# Sheet2.net
KiCad netlist of a schematic drawn in Altium Designer
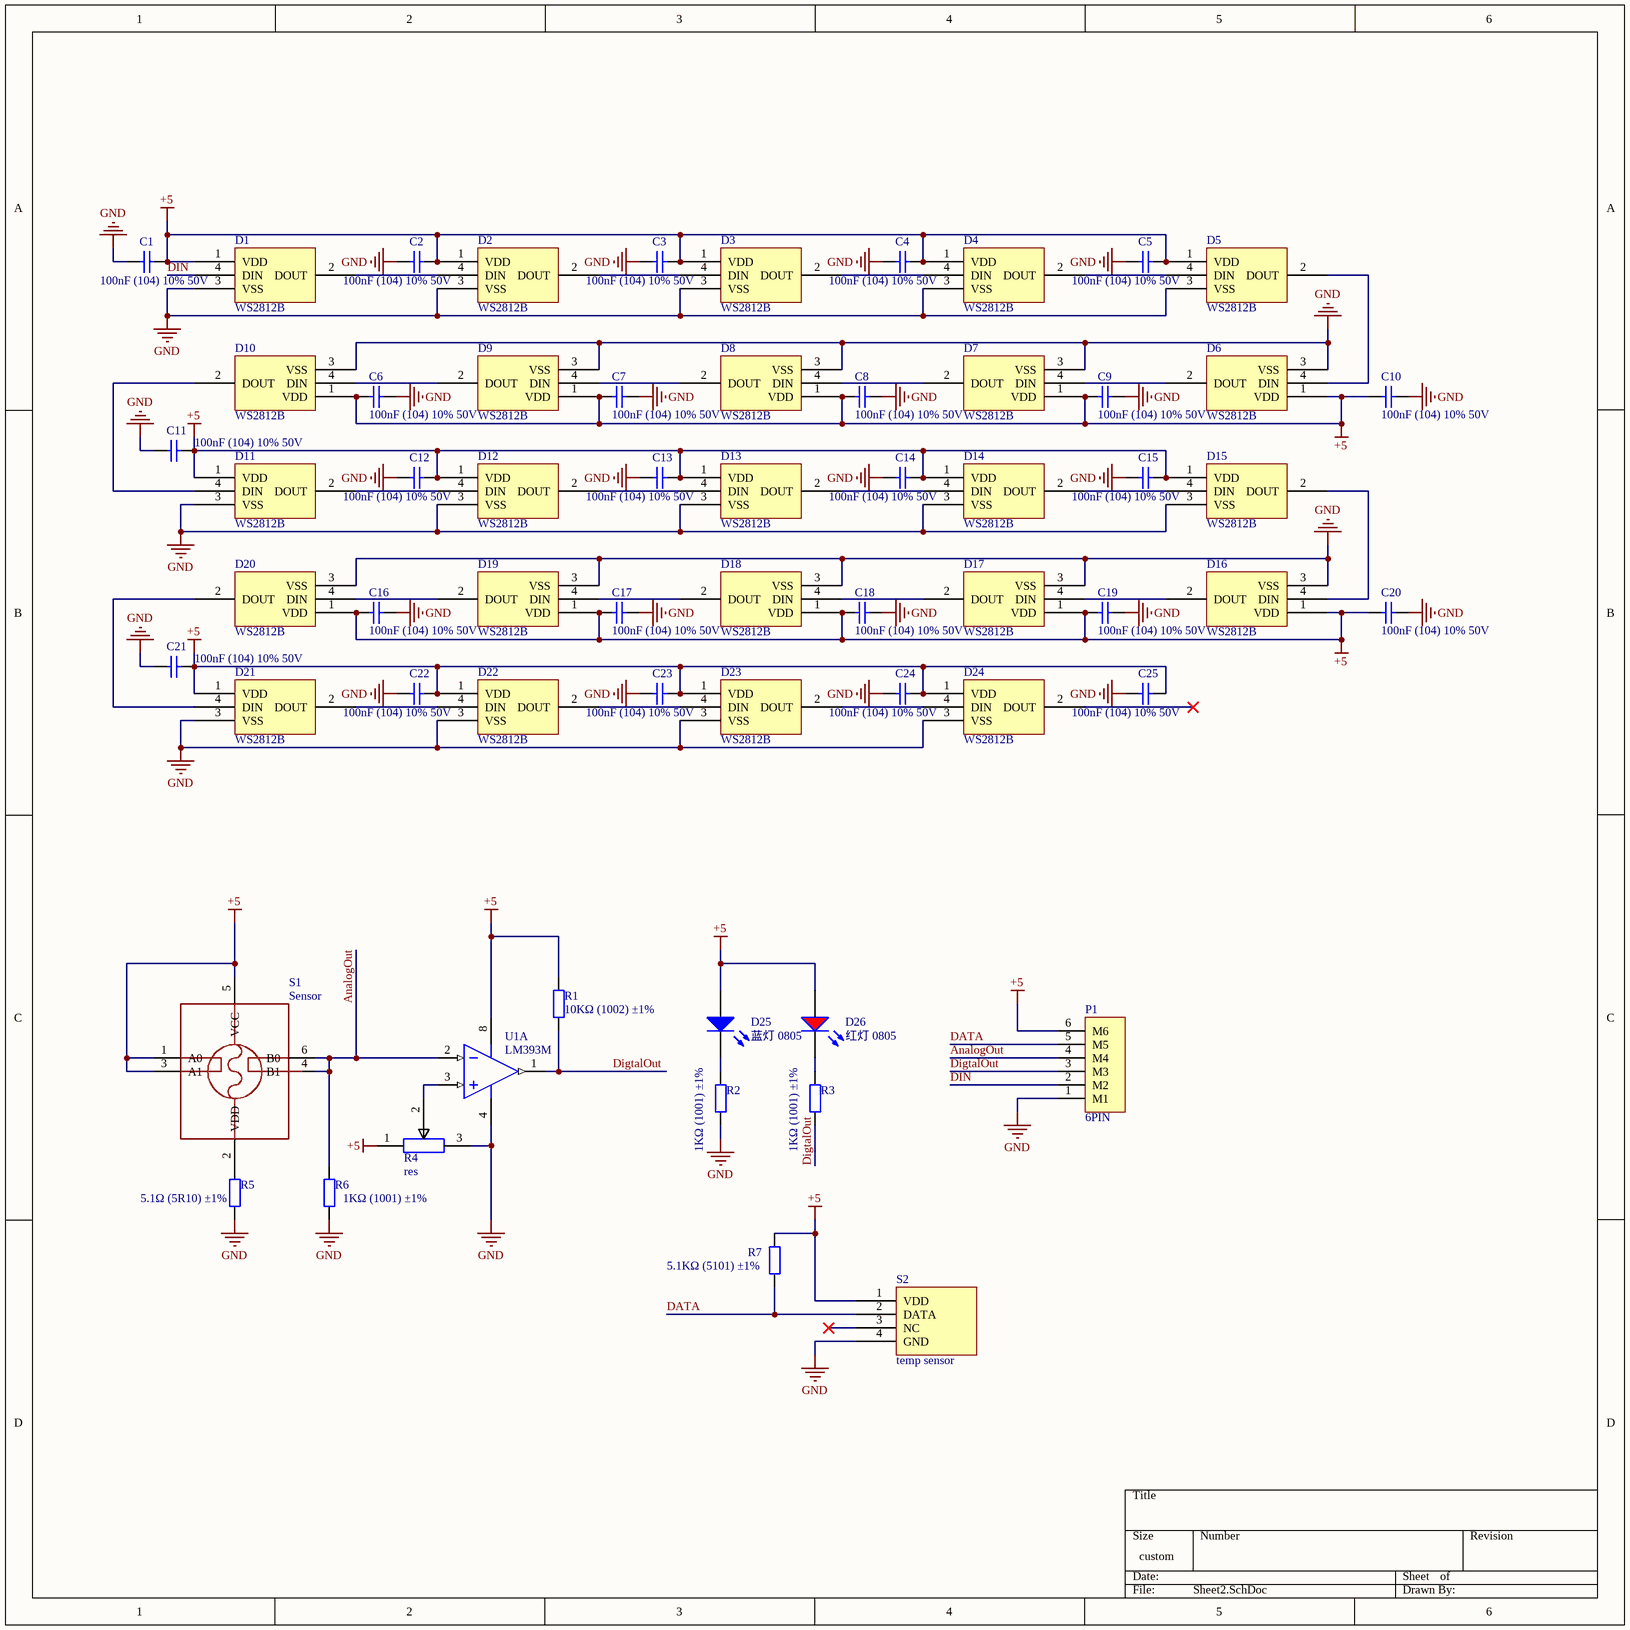
[diagram p0: Sheet2.SchDoc]

(export (version "E")
  (design (tool "Eeschema 10.0.6"))
  (components
    (comp (ref "C1")
      (value "100nF (104) 10% 50V")
      (footprint "0603_C")
      (description "贴片电容")
      (libsource (lib "Cap") (part "0603 100nF (104) 10% 50V"))
    )
    (comp (ref "C2")
      (value "100nF (104) 10% 50V")
      (footprint "0603_C")
      (description "贴片电容")
      (libsource (lib "Cap") (part "0603 100nF (104) 10% 50V"))
    )
    (comp (ref "C3")
      (value "100nF (104) 10% 50V")
      (footprint "0603_C")
      (description "贴片电容")
      (libsource (lib "Cap") (part "0603 100nF (104) 10% 50V"))
    )
    (comp (ref "C4")
      (value "100nF (104) 10% 50V")
      (footprint "0603_C")
      (description "贴片电容")
      (libsource (lib "Cap") (part "0603 100nF (104) 10% 50V"))
    )
    (comp (ref "C5")
      (value "100nF (104) 10% 50V")
      (footprint "0603_C")
      (description "贴片电容")
      (libsource (lib "Cap") (part "0603 100nF (104) 10% 50V"))
    )
    (comp (ref "C6")
      (value "100nF (104) 10% 50V")
      (footprint "0603_C")
      (description "贴片电容")
      (libsource (lib "Cap") (part "0603 100nF (104) 10% 50V"))
    )
    (comp (ref "C7")
      (value "100nF (104) 10% 50V")
      (footprint "0603_C")
      (description "贴片电容")
      (libsource (lib "Cap") (part "0603 100nF (104) 10% 50V"))
    )
    (comp (ref "C8")
      (value "100nF (104) 10% 50V")
      (footprint "0603_C")
      (description "贴片电容")
      (libsource (lib "Cap") (part "0603 100nF (104) 10% 50V"))
    )
    (comp (ref "C9")
      (value "100nF (104) 10% 50V")
      (footprint "0603_C")
      (description "贴片电容")
      (libsource (lib "Cap") (part "0603 100nF (104) 10% 50V"))
    )
    (comp (ref "C10")
      (value "100nF (104) 10% 50V")
      (footprint "0603_C")
      (description "贴片电容")
      (libsource (lib "Cap") (part "0603 100nF (104) 10% 50V"))
    )
    (comp (ref "C11")
      (value "100nF (104) 10% 50V")
      (footprint "0603_C")
      (description "贴片电容")
      (libsource (lib "Cap") (part "0603 100nF (104) 10% 50V"))
    )
    (comp (ref "C12")
      (value "100nF (104) 10% 50V")
      (footprint "0603_C")
      (description "贴片电容")
      (libsource (lib "Cap") (part "0603 100nF (104) 10% 50V"))
    )
    (comp (ref "C13")
      (value "100nF (104) 10% 50V")
      (footprint "0603_C")
      (description "贴片电容")
      (libsource (lib "Cap") (part "0603 100nF (104) 10% 50V"))
    )
    (comp (ref "C14")
      (value "100nF (104) 10% 50V")
      (footprint "0603_C")
      (description "贴片电容")
      (libsource (lib "Cap") (part "0603 100nF (104) 10% 50V"))
    )
    (comp (ref "C15")
      (value "100nF (104) 10% 50V")
      (footprint "0603_C")
      (description "贴片电容")
      (libsource (lib "Cap") (part "0603 100nF (104) 10% 50V"))
    )
    (comp (ref "C16")
      (value "100nF (104) 10% 50V")
      (footprint "0603_C")
      (description "贴片电容")
      (libsource (lib "Cap") (part "0603 100nF (104) 10% 50V"))
    )
    (comp (ref "C17")
      (value "100nF (104) 10% 50V")
      (footprint "0603_C")
      (description "贴片电容")
      (libsource (lib "Cap") (part "0603 100nF (104) 10% 50V"))
    )
    (comp (ref "C18")
      (value "100nF (104) 10% 50V")
      (footprint "0603_C")
      (description "贴片电容")
      (libsource (lib "Cap") (part "0603 100nF (104) 10% 50V"))
    )
    (comp (ref "C19")
      (value "100nF (104) 10% 50V")
      (footprint "0603_C")
      (description "贴片电容")
      (libsource (lib "Cap") (part "0603 100nF (104) 10% 50V"))
    )
    (comp (ref "C20")
      (value "100nF (104) 10% 50V")
      (footprint "0603_C")
      (description "贴片电容")
      (libsource (lib "Cap") (part "0603 100nF (104) 10% 50V"))
    )
    (comp (ref "C21")
      (value "100nF (104) 10% 50V")
      (footprint "0603_C")
      (description "贴片电容")
      (libsource (lib "Cap") (part "0603 100nF (104) 10% 50V"))
    )
    (comp (ref "C22")
      (value "100nF (104) 10% 50V")
      (footprint "0603_C")
      (description "贴片电容")
      (libsource (lib "Cap") (part "0603 100nF (104) 10% 50V"))
    )
    (comp (ref "C23")
      (value "100nF (104) 10% 50V")
      (footprint "0603_C")
      (description "贴片电容")
      (libsource (lib "Cap") (part "0603 100nF (104) 10% 50V"))
    )
    (comp (ref "C24")
      (value "100nF (104) 10% 50V")
      (footprint "0603_C")
      (description "贴片电容")
      (libsource (lib "Cap") (part "0603 100nF (104) 10% 50V"))
    )
    (comp (ref "C25")
      (value "100nF (104) 10% 50V")
      (footprint "0603_C")
      (description "贴片电容")
      (libsource (lib "Cap") (part "0603 100nF (104) 10% 50V"))
    )
    (comp (ref "D1")
      (value "WS2812B")
      (footprint "5050-4PIN-WS2812")
      (description "RGB LED IC")
      (libsource (lib "") (part "WS2812B_1"))
    )
    (comp (ref "D2")
      (value "WS2812B")
      (footprint "5050-4PIN-WS2812")
      (description "RGB LED IC")
      (libsource (lib "") (part "WS2812B_1"))
    )
    (comp (ref "D3")
      (value "WS2812B")
      (footprint "5050-4PIN-WS2812")
      (description "RGB LED IC")
      (libsource (lib "") (part "WS2812B_1"))
    )
    (comp (ref "D4")
      (value "WS2812B")
      (footprint "5050-4PIN-WS2812")
      (description "RGB LED IC")
      (libsource (lib "") (part "WS2812B_1"))
    )
    (comp (ref "D5")
      (value "WS2812B")
      (footprint "5050-4PIN-WS2812")
      (description "RGB LED IC")
      (libsource (lib "") (part "WS2812B_1"))
    )
    (comp (ref "D6")
      (value "WS2812B")
      (footprint "5050-4PIN-WS2812")
      (description "RGB LED IC")
      (libsource (lib "RGB") (part "WS2812B"))
    )
    (comp (ref "D7")
      (value "WS2812B")
      (footprint "5050-4PIN-WS2812")
      (description "RGB LED IC")
      (libsource (lib "RGB") (part "WS2812B"))
    )
    (comp (ref "D8")
      (value "WS2812B")
      (footprint "5050-4PIN-WS2812")
      (description "RGB LED IC")
      (libsource (lib "RGB") (part "WS2812B"))
    )
    (comp (ref "D9")
      (value "WS2812B")
      (footprint "5050-4PIN-WS2812")
      (description "RGB LED IC")
      (libsource (lib "RGB") (part "WS2812B"))
    )
    (comp (ref "D10")
      (value "WS2812B")
      (footprint "5050-4PIN-WS2812")
      (description "RGB LED IC")
      (libsource (lib "RGB") (part "WS2812B"))
    )
    (comp (ref "D11")
      (value "WS2812B")
      (footprint "5050-4PIN-WS2812")
      (description "RGB LED IC")
      (libsource (lib "") (part "WS2812B_1"))
    )
    (comp (ref "D12")
      (value "WS2812B")
      (footprint "5050-4PIN-WS2812")
      (description "RGB LED IC")
      (libsource (lib "") (part "WS2812B_1"))
    )
    (comp (ref "D13")
      (value "WS2812B")
      (footprint "5050-4PIN-WS2812")
      (description "RGB LED IC")
      (libsource (lib "") (part "WS2812B_1"))
    )
    (comp (ref "D14")
      (value "WS2812B")
      (footprint "5050-4PIN-WS2812")
      (description "RGB LED IC")
      (libsource (lib "") (part "WS2812B_1"))
    )
    (comp (ref "D15")
      (value "WS2812B")
      (footprint "5050-4PIN-WS2812")
      (description "RGB LED IC")
      (libsource (lib "") (part "WS2812B_1"))
    )
    (comp (ref "D16")
      (value "WS2812B")
      (footprint "5050-4PIN-WS2812")
      (description "RGB LED IC")
      (libsource (lib "RGB") (part "WS2812B"))
    )
    (comp (ref "D17")
      (value "WS2812B")
      (footprint "5050-4PIN-WS2812")
      (description "RGB LED IC")
      (libsource (lib "RGB") (part "WS2812B"))
    )
    (comp (ref "D18")
      (value "WS2812B")
      (footprint "5050-4PIN-WS2812")
      (description "RGB LED IC")
      (libsource (lib "RGB") (part "WS2812B"))
    )
    (comp (ref "D19")
      (value "WS2812B")
      (footprint "5050-4PIN-WS2812")
      (description "RGB LED IC")
      (libsource (lib "RGB") (part "WS2812B"))
    )
    (comp (ref "D20")
      (value "WS2812B")
      (footprint "5050-4PIN-WS2812")
      (description "RGB LED IC")
      (libsource (lib "RGB") (part "WS2812B"))
    )
    (comp (ref "D21")
      (value "WS2812B")
      (footprint "5050-4PIN-WS2812")
      (description "RGB LED IC")
      (libsource (lib "") (part "WS2812B_1"))
    )
    (comp (ref "D22")
      (value "WS2812B")
      (footprint "5050-4PIN-WS2812")
      (description "RGB LED IC")
      (libsource (lib "") (part "WS2812B_1"))
    )
    (comp (ref "D23")
      (value "WS2812B")
      (footprint "5050-4PIN-WS2812")
      (description "RGB LED IC")
      (libsource (lib "") (part "WS2812B_1"))
    )
    (comp (ref "D24")
      (value "WS2812B")
      (footprint "5050-4PIN-WS2812")
      (description "RGB LED IC")
      (libsource (lib "") (part "WS2812B_1"))
    )
    (comp (ref "D25")
      (value "蓝灯 0805")
      (footprint "0805_LED_S1")
      (description "发光二极管")
      (libsource (lib "LED") (part "0805 蓝灯"))
    )
    (comp (ref "D26")
      (value "红灯 0805")
      (footprint "0805_LED_S1")
      (description "发光二极管")
      (libsource (lib "LED") (part "0805 红灯"))
    )
    (comp (ref "P1")
      (value "6PIN")
      (footprint "接线端子(2.54mm)-6PIN")
      (libsource (lib "集大电协1.5") (part "接线端子-6PIN"))
    )
    (comp (ref "R1")
      (value "10KΩ (1002) ±1%")
      (footprint "0603_R")
      (description "贴片电阻")
      (libsource (lib "RES") (part "0603 10KΩ (1002) 1%"))
    )
    (comp (ref "R2")
      (value "1KΩ (1001) ±1%")
      (footprint "0603_R")
      (description "贴片电阻")
      (libsource (lib "RES") (part "0603 1KΩ (1001) 1%"))
    )
    (comp (ref "R3")
      (value "1KΩ (1001) ±1%")
      (footprint "0603_R")
      (description "贴片电阻")
      (libsource (lib "RES") (part "0603 1KΩ (1001) 1%"))
    )
    (comp (ref "R4") (value "res") (footprint "ResV") (libsource (lib "RGB") (part "RESV-10K")))
    (comp (ref "R5")
      (value "5.1Ω (5R10) ±1%")
      (footprint "0603_R")
      (description "贴片电阻")
      (libsource (lib "RES") (part "0603 5.1Ω (5R10) 1%"))
    )
    (comp (ref "R6")
      (value "1KΩ (1001) ±1%")
      (footprint "0603_R")
      (description "贴片电阻")
      (libsource (lib "") (part "0603 1KΩ (1001) 1%_1"))
    )
    (comp (ref "R7")
      (value "5.1KΩ (5101) ±1%")
      (footprint "0603_R")
      (description "贴片电阻")
      (libsource (lib "RES") (part "0603 5.1KΩ (5101) 1%"))
    )
    (comp (ref "S1") (value "Sensor") (footprint "SENSOR-TH_MQ-2") (libsource (lib "RGB") (part "MQ-2")))
    (comp (ref "S2")
      (value "temp sensor")
      (footprint "SENSOR-TH_DHT11")
      (libsource (lib "RGB") (part "DHT11"))
    )
    (comp (ref "U1")
      (value "LM393M")
      (footprint "D0008A_L")
      (description "Low Power Low Offset Voltage Dual Comparator, 8-pin Narrow SOIC")
      (fields (field (name "MANUFACTURER") "Texas Instruments"))
      (libsource (lib "Altium Content Vault") (part "AN-COMP-LM193-8"))
    )
  )
  (nets
    (net (code "1") (name "+5") (class "Default")
      (node (ref "C1") (pin "1") (pinfunction "1_1") (pintype "passive"))
      (node (ref "C10") (pin "2") (pinfunction "2_2") (pintype "passive"))
      (node (ref "C11") (pin "2") (pinfunction "2_2") (pintype "passive"))
      (node (ref "C12") (pin "2") (pinfunction "2_2") (pintype "passive"))
      (node (ref "C13") (pin "2") (pinfunction "2_2") (pintype "passive"))
      (node (ref "C14") (pin "2") (pinfunction "2_2") (pintype "passive"))
      (node (ref "C15") (pin "2") (pinfunction "2_2") (pintype "passive"))
      (node (ref "C16") (pin "1") (pinfunction "1_1") (pintype "passive"))
      (node (ref "C17") (pin "1") (pinfunction "1_1") (pintype "passive"))
      (node (ref "C18") (pin "1") (pinfunction "1_1") (pintype "passive"))
      (node (ref "C19") (pin "1") (pinfunction "1_1") (pintype "passive"))
      (node (ref "C2") (pin "1") (pinfunction "1_1") (pintype "passive"))
      (node (ref "C20") (pin "1") (pinfunction "1_1") (pintype "passive"))
      (node (ref "C21") (pin "2") (pinfunction "2_2") (pintype "passive"))
      (node (ref "C22") (pin "2") (pinfunction "2_2") (pintype "passive"))
      (node (ref "C23") (pin "2") (pinfunction "2_2") (pintype "passive"))
      (node (ref "C24") (pin "2") (pinfunction "2_2") (pintype "passive"))
      (node (ref "C25") (pin "2") (pinfunction "2_2") (pintype "passive"))
      (node (ref "C3") (pin "1") (pinfunction "1_1") (pintype "passive"))
      (node (ref "C4") (pin "1") (pinfunction "1_1") (pintype "passive"))
      (node (ref "C5") (pin "1") (pinfunction "1_1") (pintype "passive"))
      (node (ref "C6") (pin "2") (pinfunction "2_2") (pintype "passive"))
      (node (ref "C7") (pin "2") (pinfunction "2_2") (pintype "passive"))
      (node (ref "C8") (pin "2") (pinfunction "2_2") (pintype "passive"))
      (node (ref "C9") (pin "2") (pinfunction "2_2") (pintype "passive"))
      (node (ref "D1") (pin "1") (pinfunction "VDD_1") (pintype "passive"))
      (node (ref "D10") (pin "1") (pinfunction "VDD_1") (pintype "passive"))
      (node (ref "D11") (pin "1") (pinfunction "VDD_1") (pintype "passive"))
      (node (ref "D12") (pin "1") (pinfunction "VDD_1") (pintype "passive"))
      (node (ref "D13") (pin "1") (pinfunction "VDD_1") (pintype "passive"))
      (node (ref "D14") (pin "1") (pinfunction "VDD_1") (pintype "passive"))
      (node (ref "D15") (pin "1") (pinfunction "VDD_1") (pintype "passive"))
      (node (ref "D16") (pin "1") (pinfunction "VDD_1") (pintype "passive"))
      (node (ref "D17") (pin "1") (pinfunction "VDD_1") (pintype "passive"))
      (node (ref "D18") (pin "1") (pinfunction "VDD_1") (pintype "passive"))
      (node (ref "D19") (pin "1") (pinfunction "VDD_1") (pintype "passive"))
      (node (ref "D2") (pin "1") (pinfunction "VDD_1") (pintype "passive"))
      (node (ref "D20") (pin "1") (pinfunction "VDD_1") (pintype "passive"))
      (node (ref "D21") (pin "1") (pinfunction "VDD_1") (pintype "passive"))
      (node (ref "D22") (pin "1") (pinfunction "VDD_1") (pintype "passive"))
      (node (ref "D23") (pin "1") (pinfunction "VDD_1") (pintype "passive"))
      (node (ref "D24") (pin "1") (pinfunction "VDD_1") (pintype "passive"))
      (node (ref "D25") (pin "A") (pinfunction "A_A") (pintype "passive"))
      (node (ref "D26") (pin "A") (pinfunction "A_A") (pintype "passive"))
      (node (ref "D3") (pin "1") (pinfunction "VDD_1") (pintype "passive"))
      (node (ref "D4") (pin "1") (pinfunction "VDD_1") (pintype "passive"))
      (node (ref "D5") (pin "1") (pinfunction "VDD_1") (pintype "passive"))
      (node (ref "D6") (pin "1") (pinfunction "VDD_1") (pintype "passive"))
      (node (ref "D7") (pin "1") (pinfunction "VDD_1") (pintype "passive"))
      (node (ref "D8") (pin "1") (pinfunction "VDD_1") (pintype "passive"))
      (node (ref "D9") (pin "1") (pinfunction "VDD_1") (pintype "passive"))
      (node (ref "P1") (pin "6") (pinfunction "M6_6") (pintype "passive"))
      (node (ref "R1") (pin "2") (pinfunction "2_2") (pintype "passive"))
      (node (ref "R4") (pin "1") (pinfunction "1_1") (pintype "passive"))
      (node (ref "R7") (pin "2") (pinfunction "2_2") (pintype "passive"))
      (node (ref "S1") (pin "1") (pinfunction "A0_1") (pintype "passive"))
      (node (ref "S1") (pin "3") (pinfunction "A1_3") (pintype "passive"))
      (node (ref "S1") (pin "5") (pinfunction "VCC_5") (pintype "power_in"))
      (node (ref "S2") (pin "1") (pinfunction "VDD_1") (pintype "passive"))
      (node (ref "U1") (pin "8") (pinfunction "V+_8") (pintype "power_in"))
    )
    (net (code "2") (name "/AnalogOut") (class "Default")
      (node (ref "P1") (pin "4") (pinfunction "M4_4") (pintype "passive"))
      (node (ref "R6") (pin "2") (pinfunction "2_2") (pintype "passive"))
      (node (ref "S1") (pin "4") (pinfunction "B1_4") (pintype "passive"))
      (node (ref "S1") (pin "6") (pinfunction "B0_6") (pintype "passive"))
      (node (ref "U1") (pin "2") (pinfunction "INA-_2") (pintype "input"))
    )
    (net (code "3") (name "/DATA") (class "Default")
      (node (ref "P1") (pin "5") (pinfunction "M5_5") (pintype "passive"))
      (node (ref "R7") (pin "1") (pinfunction "1_1") (pintype "passive"))
      (node (ref "S2") (pin "2") (pinfunction "DATA_2") (pintype "passive"))
    )
    (net (code "4") (name "/DIN") (class "Default")
      (node (ref "D1") (pin "4") (pinfunction "DIN_4") (pintype "passive"))
      (node (ref "P1") (pin "2") (pinfunction "M2_2") (pintype "passive"))
    )
    (net (code "5") (name "/DigtalOut") (class "Default")
      (node (ref "P1") (pin "3") (pinfunction "M3_3") (pintype "passive"))
      (node (ref "R1") (pin "1") (pinfunction "1_1") (pintype "passive"))
      (node (ref "R3") (pin "2") (pinfunction "2_2") (pintype "passive"))
      (node (ref "U1") (pin "1") (pinfunction "OUTA_1") (pintype "output"))
    )
    (net (code "6") (name "GND") (class "Default")
      (node (ref "C1") (pin "2") (pinfunction "2_2") (pintype "passive"))
      (node (ref "C10") (pin "1") (pinfunction "1_1") (pintype "passive"))
      (node (ref "C11") (pin "1") (pinfunction "1_1") (pintype "passive"))
      (node (ref "C12") (pin "1") (pinfunction "1_1") (pintype "passive"))
      (node (ref "C13") (pin "1") (pinfunction "1_1") (pintype "passive"))
      (node (ref "C14") (pin "1") (pinfunction "1_1") (pintype "passive"))
      (node (ref "C15") (pin "1") (pinfunction "1_1") (pintype "passive"))
      (node (ref "C16") (pin "2") (pinfunction "2_2") (pintype "passive"))
      (node (ref "C17") (pin "2") (pinfunction "2_2") (pintype "passive"))
      (node (ref "C18") (pin "2") (pinfunction "2_2") (pintype "passive"))
      (node (ref "C19") (pin "2") (pinfunction "2_2") (pintype "passive"))
      (node (ref "C2") (pin "2") (pinfunction "2_2") (pintype "passive"))
      (node (ref "C20") (pin "2") (pinfunction "2_2") (pintype "passive"))
      (node (ref "C21") (pin "1") (pinfunction "1_1") (pintype "passive"))
      (node (ref "C22") (pin "1") (pinfunction "1_1") (pintype "passive"))
      (node (ref "C23") (pin "1") (pinfunction "1_1") (pintype "passive"))
      (node (ref "C24") (pin "1") (pinfunction "1_1") (pintype "passive"))
      (node (ref "C25") (pin "1") (pinfunction "1_1") (pintype "passive"))
      (node (ref "C3") (pin "2") (pinfunction "2_2") (pintype "passive"))
      (node (ref "C4") (pin "2") (pinfunction "2_2") (pintype "passive"))
      (node (ref "C5") (pin "2") (pinfunction "2_2") (pintype "passive"))
      (node (ref "C6") (pin "1") (pinfunction "1_1") (pintype "passive"))
      (node (ref "C7") (pin "1") (pinfunction "1_1") (pintype "passive"))
      (node (ref "C8") (pin "1") (pinfunction "1_1") (pintype "passive"))
      (node (ref "C9") (pin "1") (pinfunction "1_1") (pintype "passive"))
      (node (ref "D1") (pin "3") (pinfunction "VSS_3") (pintype "passive"))
      (node (ref "D10") (pin "3") (pinfunction "VSS_3") (pintype "passive"))
      (node (ref "D11") (pin "3") (pinfunction "VSS_3") (pintype "passive"))
      (node (ref "D12") (pin "3") (pinfunction "VSS_3") (pintype "passive"))
      (node (ref "D13") (pin "3") (pinfunction "VSS_3") (pintype "passive"))
      (node (ref "D14") (pin "3") (pinfunction "VSS_3") (pintype "passive"))
      (node (ref "D15") (pin "3") (pinfunction "VSS_3") (pintype "passive"))
      (node (ref "D16") (pin "3") (pinfunction "VSS_3") (pintype "passive"))
      (node (ref "D17") (pin "3") (pinfunction "VSS_3") (pintype "passive"))
      (node (ref "D18") (pin "3") (pinfunction "VSS_3") (pintype "passive"))
      (node (ref "D19") (pin "3") (pinfunction "VSS_3") (pintype "passive"))
      (node (ref "D2") (pin "3") (pinfunction "VSS_3") (pintype "passive"))
      (node (ref "D20") (pin "3") (pinfunction "VSS_3") (pintype "passive"))
      (node (ref "D21") (pin "3") (pinfunction "VSS_3") (pintype "passive"))
      (node (ref "D22") (pin "3") (pinfunction "VSS_3") (pintype "passive"))
      (node (ref "D23") (pin "3") (pinfunction "VSS_3") (pintype "passive"))
      (node (ref "D24") (pin "3") (pinfunction "VSS_3") (pintype "passive"))
      (node (ref "D3") (pin "3") (pinfunction "VSS_3") (pintype "passive"))
      (node (ref "D4") (pin "3") (pinfunction "VSS_3") (pintype "passive"))
      (node (ref "D5") (pin "3") (pinfunction "VSS_3") (pintype "passive"))
      (node (ref "D6") (pin "3") (pinfunction "VSS_3") (pintype "passive"))
      (node (ref "D7") (pin "3") (pinfunction "VSS_3") (pintype "passive"))
      (node (ref "D8") (pin "3") (pinfunction "VSS_3") (pintype "passive"))
      (node (ref "D9") (pin "3") (pinfunction "VSS_3") (pintype "passive"))
      (node (ref "P1") (pin "1") (pinfunction "M1_1") (pintype "passive"))
      (node (ref "R2") (pin "2") (pinfunction "2_2") (pintype "passive"))
      (node (ref "R4") (pin "3") (pinfunction "3_3") (pintype "passive"))
      (node (ref "R5") (pin "2") (pinfunction "2_2") (pintype "passive"))
      (node (ref "R6") (pin "1") (pinfunction "1_1") (pintype "passive"))
      (node (ref "S2") (pin "4") (pinfunction "GND_4") (pintype "passive"))
      (node (ref "U1") (pin "4") (pinfunction "GND_4") (pintype "power_in"))
    )
    (net (code "7") (name "Net-(D1-DOUT)") (class "Default")
      (node (ref "D1") (pin "2") (pinfunction "DOUT_2") (pintype "passive"))
      (node (ref "D2") (pin "4") (pinfunction "DIN_4") (pintype "passive"))
    )
    (net (code "8") (name "Net-(D2-DOUT)") (class "Default")
      (node (ref "D2") (pin "2") (pinfunction "DOUT_2") (pintype "passive"))
      (node (ref "D3") (pin "4") (pinfunction "DIN_4") (pintype "passive"))
    )
    (net (code "9") (name "Net-(D3-DOUT)") (class "Default")
      (node (ref "D3") (pin "2") (pinfunction "DOUT_2") (pintype "passive"))
      (node (ref "D4") (pin "4") (pinfunction "DIN_4") (pintype "passive"))
    )
    (net (code "10") (name "Net-(D4-DOUT)") (class "Default")
      (node (ref "D4") (pin "2") (pinfunction "DOUT_2") (pintype "passive"))
      (node (ref "D5") (pin "4") (pinfunction "DIN_4") (pintype "passive"))
    )
    (net (code "11") (name "Net-(D5-DOUT)") (class "Default")
      (node (ref "D5") (pin "2") (pinfunction "DOUT_2") (pintype "passive"))
      (node (ref "D6") (pin "4") (pinfunction "DIN_4") (pintype "passive"))
    )
    (net (code "12") (name "Net-(D6-DOUT)") (class "Default")
      (node (ref "D6") (pin "2") (pinfunction "DOUT_2") (pintype "passive"))
      (node (ref "D7") (pin "4") (pinfunction "DIN_4") (pintype "passive"))
    )
    (net (code "13") (name "Net-(D7-DOUT)") (class "Default")
      (node (ref "D7") (pin "2") (pinfunction "DOUT_2") (pintype "passive"))
      (node (ref "D8") (pin "4") (pinfunction "DIN_4") (pintype "passive"))
    )
    (net (code "14") (name "Net-(D8-DOUT)") (class "Default")
      (node (ref "D8") (pin "2") (pinfunction "DOUT_2") (pintype "passive"))
      (node (ref "D9") (pin "4") (pinfunction "DIN_4") (pintype "passive"))
    )
    (net (code "15") (name "Net-(D10-DIN)") (class "Default")
      (node (ref "D10") (pin "4") (pinfunction "DIN_4") (pintype "passive"))
      (node (ref "D9") (pin "2") (pinfunction "DOUT_2") (pintype "passive"))
    )
    (net (code "16") (name "Net-(D10-DOUT)") (class "Default")
      (node (ref "D10") (pin "2") (pinfunction "DOUT_2") (pintype "passive"))
      (node (ref "D11") (pin "4") (pinfunction "DIN_4") (pintype "passive"))
    )
    (net (code "17") (name "Net-(D11-DOUT)") (class "Default")
      (node (ref "D11") (pin "2") (pinfunction "DOUT_2") (pintype "passive"))
      (node (ref "D12") (pin "4") (pinfunction "DIN_4") (pintype "passive"))
    )
    (net (code "18") (name "Net-(D12-DOUT)") (class "Default")
      (node (ref "D12") (pin "2") (pinfunction "DOUT_2") (pintype "passive"))
      (node (ref "D13") (pin "4") (pinfunction "DIN_4") (pintype "passive"))
    )
    (net (code "19") (name "Net-(D13-DOUT)") (class "Default")
      (node (ref "D13") (pin "2") (pinfunction "DOUT_2") (pintype "passive"))
      (node (ref "D14") (pin "4") (pinfunction "DIN_4") (pintype "passive"))
    )
    (net (code "20") (name "Net-(D14-DOUT)") (class "Default")
      (node (ref "D14") (pin "2") (pinfunction "DOUT_2") (pintype "passive"))
      (node (ref "D15") (pin "4") (pinfunction "DIN_4") (pintype "passive"))
    )
    (net (code "21") (name "Net-(D15-DOUT)") (class "Default")
      (node (ref "D15") (pin "2") (pinfunction "DOUT_2") (pintype "passive"))
      (node (ref "D16") (pin "4") (pinfunction "DIN_4") (pintype "passive"))
    )
    (net (code "22") (name "Net-(D16-DOUT)") (class "Default")
      (node (ref "D16") (pin "2") (pinfunction "DOUT_2") (pintype "passive"))
      (node (ref "D17") (pin "4") (pinfunction "DIN_4") (pintype "passive"))
    )
    (net (code "23") (name "Net-(D17-DOUT)") (class "Default")
      (node (ref "D17") (pin "2") (pinfunction "DOUT_2") (pintype "passive"))
      (node (ref "D18") (pin "4") (pinfunction "DIN_4") (pintype "passive"))
    )
    (net (code "24") (name "Net-(D18-DOUT)") (class "Default")
      (node (ref "D18") (pin "2") (pinfunction "DOUT_2") (pintype "passive"))
      (node (ref "D19") (pin "4") (pinfunction "DIN_4") (pintype "passive"))
    )
    (net (code "25") (name "Net-(D19-DOUT)") (class "Default")
      (node (ref "D19") (pin "2") (pinfunction "DOUT_2") (pintype "passive"))
      (node (ref "D20") (pin "4") (pinfunction "DIN_4") (pintype "passive"))
    )
    (net (code "26") (name "Net-(D20-DOUT)") (class "Default")
      (node (ref "D20") (pin "2") (pinfunction "DOUT_2") (pintype "passive"))
      (node (ref "D21") (pin "4") (pinfunction "DIN_4") (pintype "passive"))
    )
    (net (code "27") (name "Net-(D21-DOUT)") (class "Default")
      (node (ref "D21") (pin "2") (pinfunction "DOUT_2") (pintype "passive"))
      (node (ref "D22") (pin "4") (pinfunction "DIN_4") (pintype "passive"))
    )
    (net (code "28") (name "Net-(D22-DOUT)") (class "Default")
      (node (ref "D22") (pin "2") (pinfunction "DOUT_2") (pintype "passive"))
      (node (ref "D23") (pin "4") (pinfunction "DIN_4") (pintype "passive"))
    )
    (net (code "29") (name "Net-(D23-DOUT)") (class "Default")
      (node (ref "D23") (pin "2") (pinfunction "DOUT_2") (pintype "passive"))
      (node (ref "D24") (pin "4") (pinfunction "DIN_4") (pintype "passive"))
    )
    (net (code "30") (name "Net-(D25-PadK)") (class "Default")
      (node (ref "D25") (pin "K") (pinfunction "K_K") (pintype "passive"))
      (node (ref "R2") (pin "1") (pinfunction "1_1") (pintype "passive"))
    )
    (net (code "31") (name "Net-(D26-PadK)") (class "Default")
      (node (ref "D26") (pin "K") (pinfunction "K_K") (pintype "passive"))
      (node (ref "R3") (pin "1") (pinfunction "1_1") (pintype "passive"))
    )
    (net (code "32") (name "Net-(S1-VDD)") (class "Default")
      (node (ref "R5") (pin "1") (pinfunction "1_1") (pintype "passive"))
      (node (ref "S1") (pin "2") (pinfunction "VDD_2") (pintype "passive"))
    )
    (net (code "33") (name "Net-(U1A-INA+)") (class "Default")
      (node (ref "R4") (pin "2") (pinfunction "2_2") (pintype "passive"))
      (node (ref "U1") (pin "3") (pinfunction "INA+_3") (pintype "input"))
    )
    (net (code "34") (name "unconnected-(D24-DOUT-Pad2)") (class "Default")
      (node (ref "D24") (pin "2") (pinfunction "DOUT_2") (pintype "passive+no_connect"))
    )
    (net (code "35") (name "unconnected-(S2-NC-Pad3)") (class "Default")
      (node (ref "S2") (pin "3") (pinfunction "NC_3") (pintype "passive+no_connect"))
    )
  )
)
